# lab_1_zhernakov_usb_rs232.net
KiCad netlist of a schematic drawn in Altium Designer
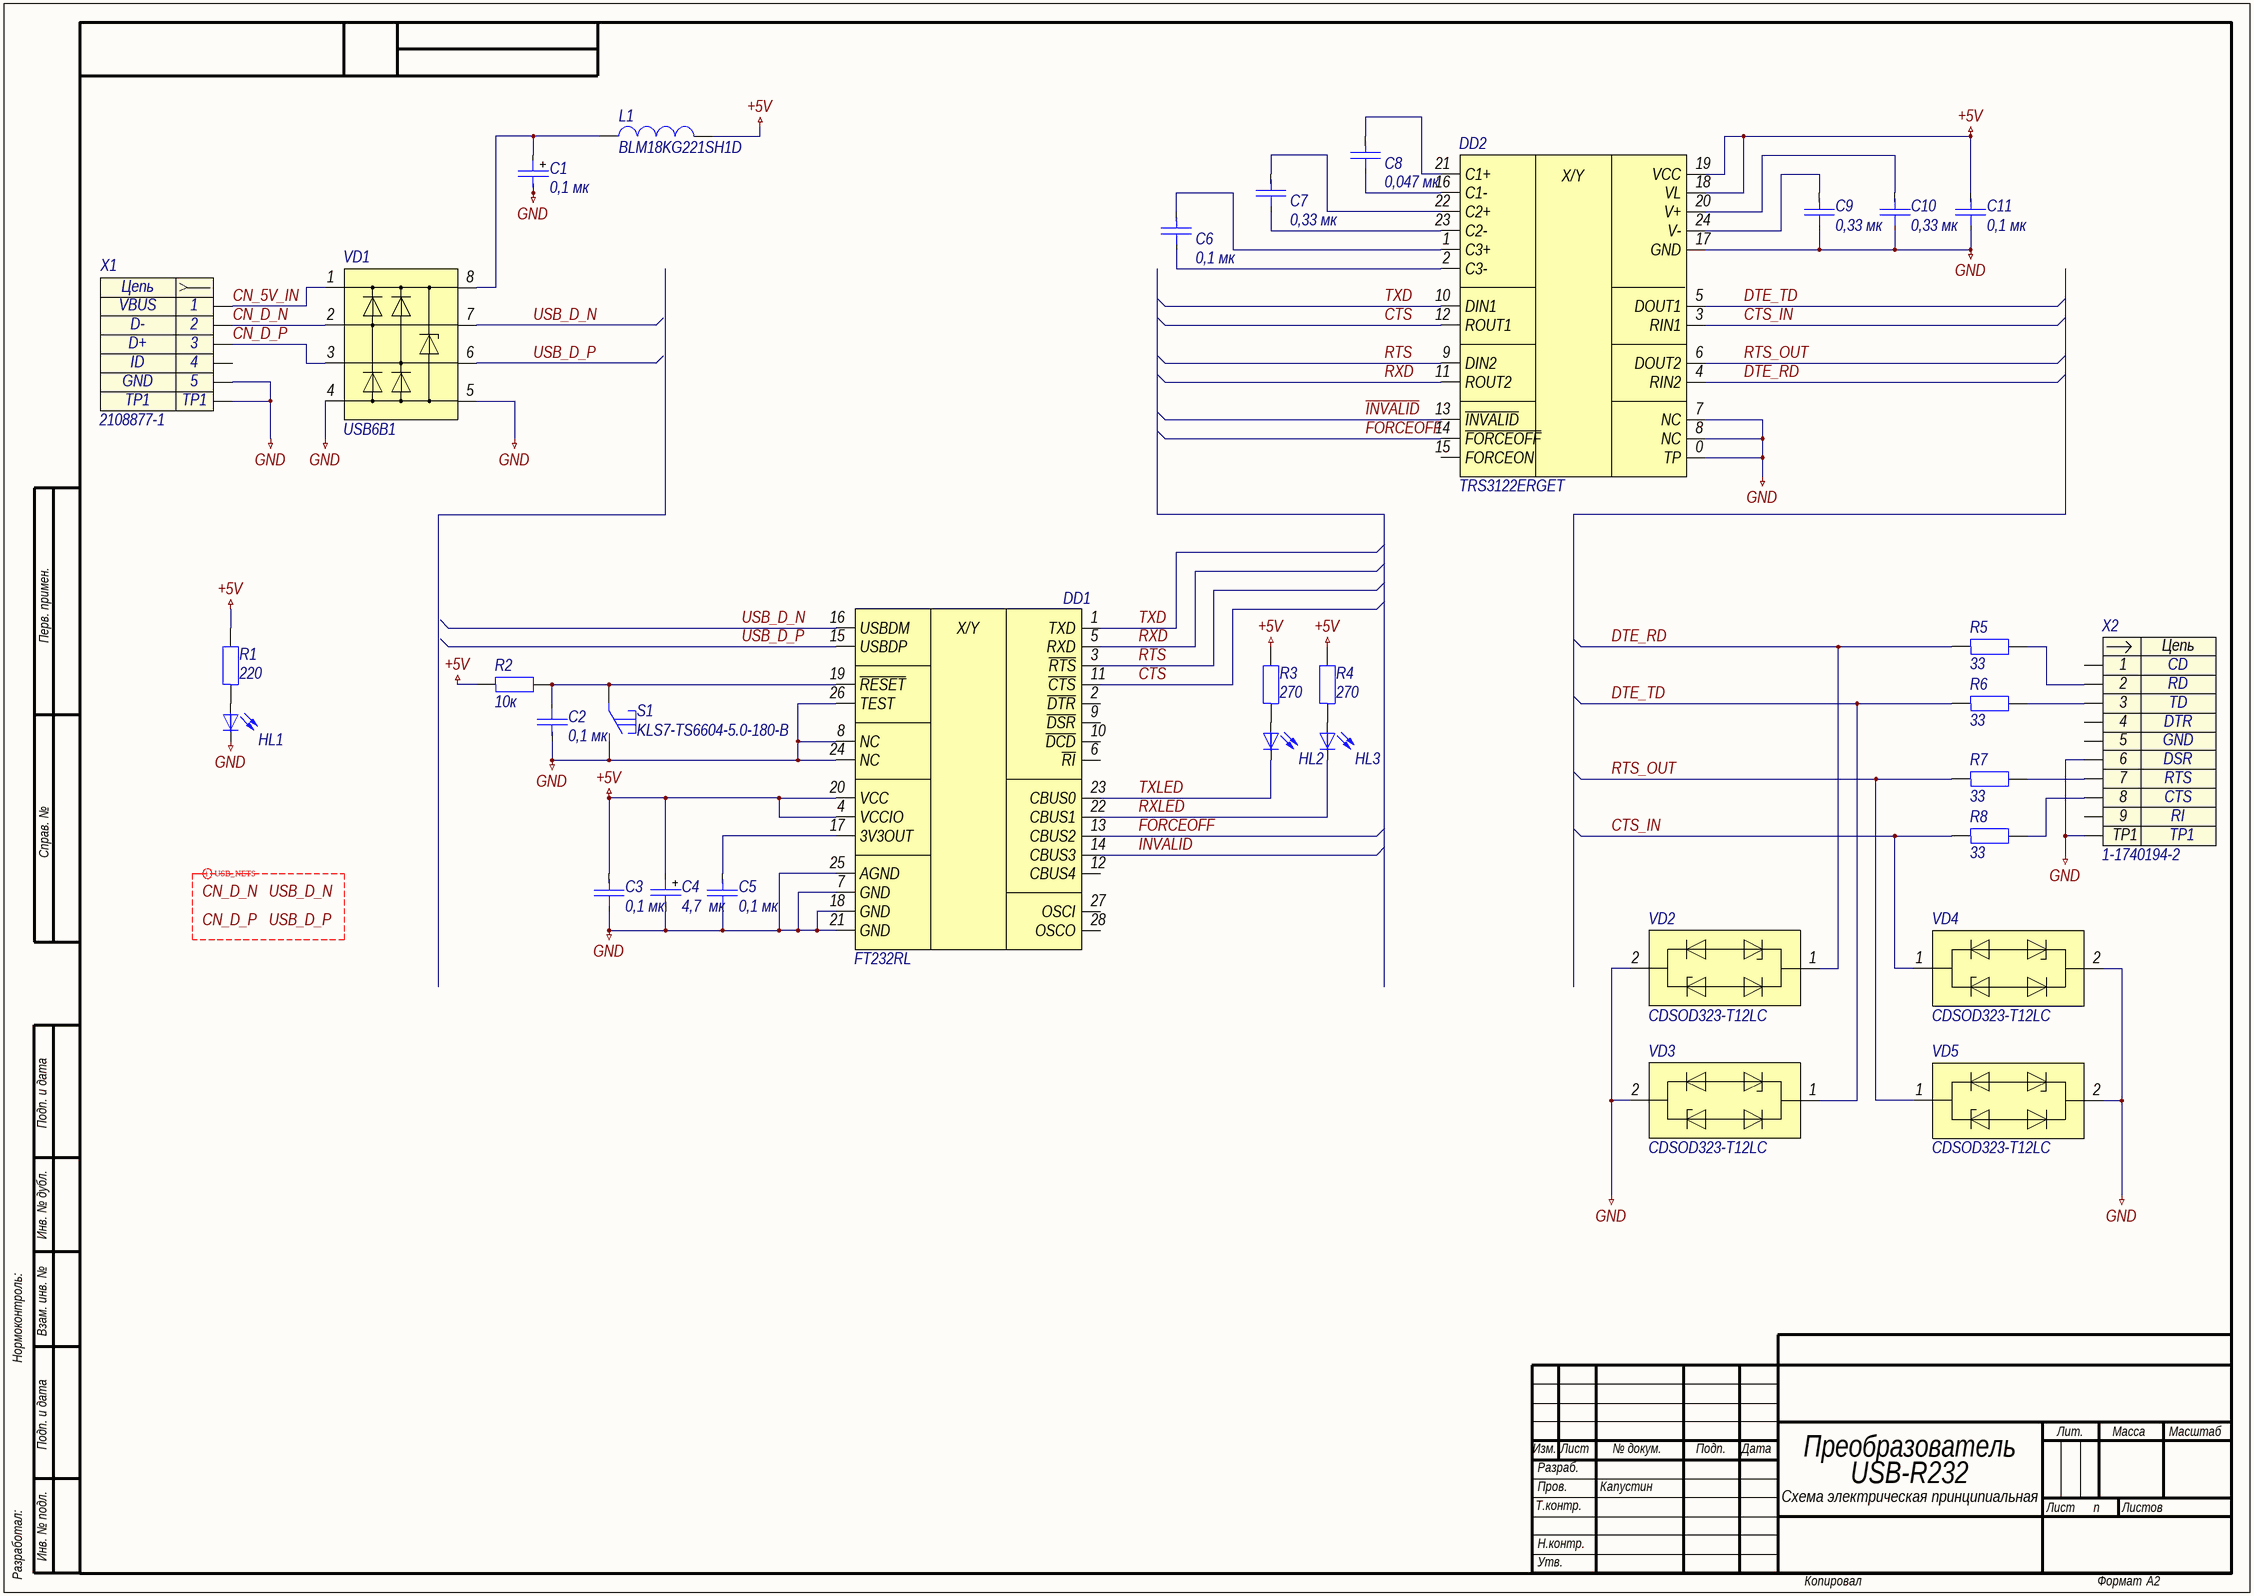
[diagram p0: lab_1_zhernakov_usb_rs232.SchDoc]

(export (version "E")
  (design (tool "Eeschema 10.0.6"))
  (components
    (comp (ref "C1")
      (value "0,1 мк")
      (footprint "C3216-18")
      (description "=Описание")
      (libsource (lib "Database_Students") (part "C-25.0V"))
    )
    (comp (ref "C2")
      (value "0,1 мк")
      (footprint "C0603")
      (description "=Описание")
      (libsource (lib "Database_Students") (part "C-50.0V"))
    )
    (comp (ref "C3")
      (value "0,1 мк")
      (footprint "C0603")
      (description "=Описание")
      (libsource (lib "Database_Students") (part "C-50.0V"))
    )
    (comp (ref "C4")
      (value "4,7  мк")
      (footprint "C3216-18")
      (description "=Описание")
      (libsource (lib "Database_Students") (part "C-25.0V"))
    )
    (comp (ref "C5")
      (value "0,1 мк")
      (footprint "c0805:C0805")
      (description "=Описание")
      (libsource (lib "Database_Students") (part "C-50.0V"))
    )
    (comp (ref "C6")
      (value "0,1 мк")
      (footprint "C0603")
      (description "=Описание")
      (libsource (lib "Database_Students") (part "C-50.0V"))
    )
    (comp (ref "C7")
      (value "0,33 мк")
      (footprint "C0805")
      (description "=Описание")
      (libsource (lib "Database_Students") (part "C-50.0V"))
    )
    (comp (ref "C8")
      (value "0,047 мк")
      (footprint "C0603")
      (description "=Описание")
      (libsource (lib "Database_Students") (part "C-50.0V"))
    )
    (comp (ref "C9")
      (value "0,33 мк")
      (footprint "C0805")
      (description "=Описание")
      (libsource (lib "Database_Students") (part "C-50.0V"))
    )
    (comp (ref "C10")
      (value "0,33 мк")
      (footprint "C0805")
      (description "=Описание")
      (libsource (lib "Database_Students") (part "C-50.0V"))
    )
    (comp (ref "C11")
      (value "0,1 мк")
      (footprint "C0603")
      (description "=Описание")
      (libsource (lib "Database_Students") (part "C-50.0V"))
    )
    (comp (ref "DD1")
      (value "FT232RL")
      (footprint "SSOP-28")
      (description "=Описание")
      (libsource (lib "Database_Students") (part "FT232RL"))
    )
    (comp (ref "DD2")
      (value "TRS3122ERGET")
      (footprint "QFN-24-400x400x100")
      (description "=Описание")
      (libsource (lib "Database_Students") (part "TRS3122ERGET"))
    )
    (comp (ref "HL1")
      (value "~")
      (footprint "D0603")
      (description "=Описание")
      (libsource (lib "Database_Students") (part "L0001"))
    )
    (comp (ref "HL2")
      (value "~")
      (footprint "D0603")
      (description "=Описание")
      (libsource (lib "Database_Students") (part "L0001"))
    )
    (comp (ref "HL3")
      (value "~")
      (footprint "D0603")
      (description "=Описание")
      (libsource (lib "Database_Students") (part "L0001"))
    )
    (comp (ref "L1")
      (value "BLM18KG221SH1D")
      (footprint "FERRITE-BEAD")
      (description "=Описание")
      (libsource (lib "Database_Students") (part "FERRITE-BEAD"))
    )
    (comp (ref "R1")
      (value "220")
      (footprint "R0603")
      (description "=Описание")
      (libsource (lib "Database_Students") (part "R-0.05W"))
    )
    (comp (ref "R2")
      (value "10к")
      (footprint "R0603")
      (description "=Описание")
      (libsource (lib "Database_Students") (part "R-0.05W"))
    )
    (comp (ref "R3")
      (value "270")
      (footprint "R0603")
      (description "=Описание")
      (libsource (lib "Database_Students") (part "R-0.05W"))
    )
    (comp (ref "R4")
      (value "270")
      (footprint "R0603")
      (description "=Описание")
      (libsource (lib "Database_Students") (part "R-0.05W"))
    )
    (comp (ref "R5")
      (value "33")
      (footprint "R0603")
      (description "=Описание")
      (libsource (lib "Database_Students") (part "R-0.05W"))
    )
    (comp (ref "R6")
      (value "33")
      (footprint "R0603")
      (description "=Описание")
      (libsource (lib "Database_Students") (part "R-0.05W"))
    )
    (comp (ref "R7")
      (value "33")
      (footprint "R0603")
      (description "=Описание")
      (libsource (lib "Database_Students") (part "R-0.05W"))
    )
    (comp (ref "R8")
      (value "33")
      (footprint "R0603")
      (description "=Описание")
      (libsource (lib "Database_Students") (part "R-0.05W"))
    )
    (comp (ref "S1")
      (value "KLS7-TS6604-5.0-180-B")
      (footprint "KLS7-TS6604-5.0-180-B")
      (description "=Описание")
      (libsource (lib "Database_Students") (part "BUTTON"))
    )
    (comp (ref "VD1")
      (value "USB6B1")
      (footprint "SO-8")
      (libsource (lib "Database_Students") (part "asmvd0007"))
    )
    (comp (ref "VD2")
      (value "CDSOD323-T12LC")
      (footprint "SOD-323")
      (description "=Описание")
      (libsource (lib "") (part "CDSOD323-T12LC_1"))
    )
    (comp (ref "VD3")
      (value "CDSOD323-T12LC")
      (footprint "SOD-323")
      (description "=Описание")
      (libsource (lib "") (part "CDSOD323-T12LC_1"))
    )
    (comp (ref "VD4")
      (value "CDSOD323-T12LC")
      (footprint "SOD-323")
      (description "=Описание")
      (libsource (lib "Database_Students") (part "CDSOD323-T12LC"))
    )
    (comp (ref "VD5")
      (value "CDSOD323-T12LC")
      (footprint "SOD-323")
      (description "=Описание")
      (libsource (lib "Database_Students") (part "CDSOD323-T12LC"))
    )
    (comp (ref "X1")
      (value "2108877-1")
      (footprint "2108877-1")
      (libsource (lib "2108877-1_micro_usb-b") (part "2108877-1_micro_usb-b"))
    )
    (comp (ref "X2")
      (value "1-1740194-2")
      (footprint "1-1740194-2")
      (libsource (lib "Database_Students") (part "HEADER-9-TP1-SCT"))
    )
  )
  (nets
    (net (code "1") (name "+5V") (class "Default")
      (node (ref "C11") (pin "2") (pinfunction "2_2") (pintype "passive"))
      (node (ref "C3") (pin "2") (pinfunction "2_2") (pintype "passive"))
      (node (ref "C4") (pin "1") (pinfunction "1_1") (pintype "passive"))
      (node (ref "DD1") (pin "20") (pinfunction "VCC_20") (pintype "passive"))
      (node (ref "DD1") (pin "4") (pinfunction "VCCIO_4") (pintype "passive"))
      (node (ref "DD2") (pin "18") (pinfunction "VL_18") (pintype "passive"))
      (node (ref "DD2") (pin "19") (pinfunction "VCC_19") (pintype "passive"))
      (node (ref "L1") (pin "2") (pinfunction "2_2") (pintype "passive"))
      (node (ref "R1") (pin "2") (pinfunction "2_2") (pintype "passive"))
      (node (ref "R2") (pin "1") (pinfunction "1_1") (pintype "passive"))
      (node (ref "R3") (pin "2") (pinfunction "2_2") (pintype "passive"))
      (node (ref "R4") (pin "2") (pinfunction "2_2") (pintype "passive"))
    )
    (net (code "2") (name "/CN_5V_IN") (class "Default")
      (node (ref "VD1") (pin "1") (pintype "passive"))
      (node (ref "X1") (pin "1") (pinfunction "1_1") (pintype "passive"))
    )
    (net (code "3") (name "/CN_D_N") (class "Default")
      (node (ref "VD1") (pin "2") (pintype "passive"))
      (node (ref "X1") (pin "2") (pinfunction "2_2") (pintype "passive"))
    )
    (net (code "4") (name "/CN_D_P") (class "Default")
      (node (ref "VD1") (pin "3") (pintype "passive"))
      (node (ref "X1") (pin "3") (pinfunction "3_3") (pintype "passive"))
    )
    (net (code "5") (name "/CTS") (class "Default")
      (node (ref "DD1") (pin "11") (pinfunction "~{CTS}_11") (pintype "passive"))
      (node (ref "DD2") (pin "12") (pinfunction "ROUT1_12") (pintype "passive"))
    )
    (net (code "6") (name "/CTS_IN") (class "Default")
      (node (ref "DD2") (pin "3") (pinfunction "RIN1_3") (pintype "passive"))
      (node (ref "R8") (pin "1") (pinfunction "1_1") (pintype "passive"))
      (node (ref "VD4") (pin "1") (pintype "passive"))
    )
    (net (code "7") (name "/DTE_RD") (class "Default")
      (node (ref "DD2") (pin "4") (pinfunction "RIN2_4") (pintype "passive"))
      (node (ref "R5") (pin "1") (pinfunction "1_1") (pintype "passive"))
      (node (ref "VD2") (pin "1") (pintype "passive"))
    )
    (net (code "8") (name "/DTE_TD") (class "Default")
      (node (ref "DD2") (pin "5") (pinfunction "DOUT1_5") (pintype "passive"))
      (node (ref "R6") (pin "1") (pinfunction "1_1") (pintype "passive"))
      (node (ref "VD3") (pin "1") (pintype "passive"))
    )
    (net (code "9") (name "/RTS") (class "Default")
      (node (ref "DD1") (pin "3") (pinfunction "~{RTS}_3") (pintype "passive"))
      (node (ref "DD2") (pin "9") (pinfunction "DIN2_9") (pintype "passive"))
    )
    (net (code "10") (name "/RTS_OUT") (class "Default")
      (node (ref "DD2") (pin "6") (pinfunction "DOUT2_6") (pintype "passive"))
      (node (ref "R7") (pin "1") (pinfunction "1_1") (pintype "passive"))
      (node (ref "VD5") (pin "1") (pintype "passive"))
    )
    (net (code "11") (name "/RXD") (class "Default")
      (node (ref "DD1") (pin "5") (pinfunction "RXD_5") (pintype "passive"))
      (node (ref "DD2") (pin "11") (pinfunction "ROUT2_11") (pintype "passive"))
    )
    (net (code "12") (name "/RXLED") (class "Default")
      (node (ref "DD1") (pin "22") (pinfunction "CBUS1_22") (pintype "passive"))
      (node (ref "HL3") (pin "2") (pinfunction "K_2") (pintype "passive"))
    )
    (net (code "13") (name "/TXD") (class "Default")
      (node (ref "DD1") (pin "1") (pinfunction "TXD_1") (pintype "passive"))
      (node (ref "DD2") (pin "10") (pinfunction "DIN1_10") (pintype "passive"))
    )
    (net (code "14") (name "/TXLED") (class "Default")
      (node (ref "DD1") (pin "23") (pinfunction "CBUS0_23") (pintype "passive"))
      (node (ref "HL2") (pin "2") (pinfunction "K_2") (pintype "passive"))
    )
    (net (code "15") (name "/USB_D_N") (class "Default")
      (node (ref "DD1") (pin "16") (pinfunction "USBDM_16") (pintype "passive"))
      (node (ref "VD1") (pin "7") (pintype "passive"))
    )
    (net (code "16") (name "/USB_D_P") (class "Default")
      (node (ref "DD1") (pin "15") (pinfunction "USBDP_15") (pintype "passive"))
      (node (ref "VD1") (pin "6") (pintype "passive"))
    )
    (net (code "17") (name "/~{FORCEOFF}") (class "Default")
      (node (ref "DD1") (pin "13") (pinfunction "CBUS2_13") (pintype "passive"))
      (node (ref "DD2") (pin "14") (pinfunction "~{FORCEOFF}_14") (pintype "passive"))
    )
    (net (code "18") (name "/~{INVALID}") (class "Default")
      (node (ref "DD1") (pin "14") (pinfunction "CBUS3_14") (pintype "passive"))
      (node (ref "DD2") (pin "13") (pinfunction "~{INVALID}_13") (pintype "passive"))
    )
    (net (code "19") (name "GND") (class "Default")
      (node (ref "C1") (pin "2") (pinfunction "2_2") (pintype "passive"))
      (node (ref "C10") (pin "1") (pinfunction "1_1") (pintype "passive"))
      (node (ref "C11") (pin "1") (pinfunction "1_1") (pintype "passive"))
      (node (ref "C2") (pin "2") (pinfunction "2_2") (pintype "passive"))
      (node (ref "C3") (pin "1") (pinfunction "1_1") (pintype "passive"))
      (node (ref "C4") (pin "2") (pinfunction "2_2") (pintype "passive"))
      (node (ref "C5") (pin "1") (pinfunction "1_1") (pintype "passive"))
      (node (ref "C9") (pin "1") (pinfunction "1_1") (pintype "passive"))
      (node (ref "DD1") (pin "18") (pinfunction "GND_18") (pintype "passive"))
      (node (ref "DD1") (pin "21") (pinfunction "GND_21") (pintype "passive"))
      (node (ref "DD1") (pin "24") (pinfunction "NC_24") (pintype "passive"))
      (node (ref "DD1") (pin "25") (pinfunction "AGND_25") (pintype "passive"))
      (node (ref "DD1") (pin "26") (pinfunction "TEST_26") (pintype "passive"))
      (node (ref "DD1") (pin "7") (pinfunction "GND_7") (pintype "passive"))
      (node (ref "DD1") (pin "8") (pinfunction "NC_8") (pintype "passive"))
      (node (ref "DD2") (pin "0") (pinfunction "TP_0") (pintype "passive"))
      (node (ref "DD2") (pin "17") (pinfunction "GND_17") (pintype "passive"))
      (node (ref "DD2") (pin "7") (pinfunction "NC_7") (pintype "passive"))
      (node (ref "DD2") (pin "8") (pinfunction "NC_8") (pintype "passive"))
      (node (ref "HL1") (pin "2") (pinfunction "K_2") (pintype "passive"))
      (node (ref "S1") (pin "2") (pinfunction "2_2") (pintype "passive"))
      (node (ref "VD1") (pin "4") (pintype "passive"))
      (node (ref "VD1") (pin "5") (pintype "passive"))
      (node (ref "VD2") (pin "2") (pintype "passive"))
      (node (ref "VD3") (pin "2") (pintype "passive"))
      (node (ref "VD4") (pin "2") (pintype "passive"))
      (node (ref "VD5") (pin "2") (pintype "passive"))
      (node (ref "X1") (pin "5") (pinfunction "5_5") (pintype "passive"))
      (node (ref "X1") (pin "TP1") (pinfunction "TP1_TP1") (pintype "passive"))
      (node (ref "X2") (pin "6") (pinfunction "6_6") (pintype "passive"))
      (node (ref "X2") (pin "TP1") (pinfunction "TP1_TP1") (pintype "passive"))
    )
    (net (code "20") (name "Net-(C1-Pad1)") (class "Default")
      (node (ref "C1") (pin "1") (pinfunction "1_1") (pintype "passive"))
      (node (ref "L1") (pin "1") (pinfunction "1_1") (pintype "passive"))
      (node (ref "VD1") (pin "8") (pintype "passive"))
    )
    (net (code "21") (name "Net-(DD1-3V3OUT)") (class "Default")
      (node (ref "C5") (pin "2") (pinfunction "2_2") (pintype "passive"))
      (node (ref "DD1") (pin "17") (pinfunction "3V3OUT_17") (pintype "passive"))
    )
    (net (code "22") (name "Net-(DD1-~{RESET})") (class "Default")
      (node (ref "C2") (pin "1") (pinfunction "1_1") (pintype "passive"))
      (node (ref "DD1") (pin "19") (pinfunction "~{RESET}_19") (pintype "passive"))
      (node (ref "R2") (pin "2") (pinfunction "2_2") (pintype "passive"))
      (node (ref "S1") (pin "1") (pinfunction "1_1") (pintype "passive"))
    )
    (net (code "23") (name "Net-(DD2-C1+)") (class "Default")
      (node (ref "C8") (pin "2") (pinfunction "2_2") (pintype "passive"))
      (node (ref "DD2") (pin "21") (pinfunction "C1+_21") (pintype "passive"))
    )
    (net (code "24") (name "Net-(DD2-C1-)") (class "Default")
      (node (ref "C8") (pin "1") (pinfunction "1_1") (pintype "passive"))
      (node (ref "DD2") (pin "16") (pinfunction "C1-_16") (pintype "passive"))
    )
    (net (code "25") (name "Net-(DD2-C2+)") (class "Default")
      (node (ref "C7") (pin "2") (pinfunction "2_2") (pintype "passive"))
      (node (ref "DD2") (pin "22") (pinfunction "C2+_22") (pintype "passive"))
    )
    (net (code "26") (name "Net-(DD2-C2-)") (class "Default")
      (node (ref "C7") (pin "1") (pinfunction "1_1") (pintype "passive"))
      (node (ref "DD2") (pin "23") (pinfunction "C2-_23") (pintype "passive"))
    )
    (net (code "27") (name "Net-(DD2-C3+)") (class "Default")
      (node (ref "C6") (pin "2") (pinfunction "2_2") (pintype "passive"))
      (node (ref "DD2") (pin "1") (pinfunction "C3+_1") (pintype "passive"))
    )
    (net (code "28") (name "Net-(DD2-C3-)") (class "Default")
      (node (ref "C6") (pin "1") (pinfunction "1_1") (pintype "passive"))
      (node (ref "DD2") (pin "2") (pinfunction "C3-_2") (pintype "passive"))
    )
    (net (code "29") (name "Net-(DD2-V+)") (class "Default")
      (node (ref "C10") (pin "2") (pinfunction "2_2") (pintype "passive"))
      (node (ref "DD2") (pin "20") (pinfunction "V+_20") (pintype "passive"))
    )
    (net (code "30") (name "Net-(DD2-V-)") (class "Default")
      (node (ref "C9") (pin "2") (pinfunction "2_2") (pintype "passive"))
      (node (ref "DD2") (pin "24") (pinfunction "V-_24") (pintype "passive"))
    )
    (net (code "31") (name "Net-(HL1-A)") (class "Default")
      (node (ref "HL1") (pin "1") (pinfunction "A_1") (pintype "passive"))
      (node (ref "R1") (pin "1") (pinfunction "1_1") (pintype "passive"))
    )
    (net (code "32") (name "Net-(HL2-A)") (class "Default")
      (node (ref "HL2") (pin "1") (pinfunction "A_1") (pintype "passive"))
      (node (ref "R3") (pin "1") (pinfunction "1_1") (pintype "passive"))
    )
    (net (code "33") (name "Net-(HL3-A)") (class "Default")
      (node (ref "HL3") (pin "1") (pinfunction "A_1") (pintype "passive"))
      (node (ref "R4") (pin "1") (pinfunction "1_1") (pintype "passive"))
    )
    (net (code "34") (name "Net-(R5-Pad2)") (class "Default")
      (node (ref "R5") (pin "2") (pinfunction "2_2") (pintype "passive"))
      (node (ref "X2") (pin "2") (pinfunction "2_2") (pintype "passive"))
    )
    (net (code "35") (name "Net-(R6-Pad2)") (class "Default")
      (node (ref "R6") (pin "2") (pinfunction "2_2") (pintype "passive"))
      (node (ref "X2") (pin "3") (pinfunction "3_3") (pintype "passive"))
    )
    (net (code "36") (name "Net-(R7-Pad2)") (class "Default")
      (node (ref "R7") (pin "2") (pinfunction "2_2") (pintype "passive"))
      (node (ref "X2") (pin "7") (pinfunction "7_7") (pintype "passive"))
    )
    (net (code "37") (name "Net-(R8-Pad2)") (class "Default")
      (node (ref "R8") (pin "2") (pinfunction "2_2") (pintype "passive"))
      (node (ref "X2") (pin "8") (pinfunction "8_8") (pintype "passive"))
    )
    (net (code "38") (name "unconnected-(DD1-CBUS4-Pad12)") (class "Default")
      (node (ref "DD1") (pin "12") (pinfunction "CBUS4_12") (pintype "passive"))
    )
    (net (code "39") (name "unconnected-(DD1-OSCI-Pad27)") (class "Default")
      (node (ref "DD1") (pin "27") (pinfunction "OSCI_27") (pintype "passive"))
    )
    (net (code "40") (name "unconnected-(DD1-OSCO-Pad28)") (class "Default")
      (node (ref "DD1") (pin "28") (pinfunction "OSCO_28") (pintype "passive"))
    )
    (net (code "41") (name "unconnected-(DD1-~{DCD}-Pad10)") (class "Default")
      (node (ref "DD1") (pin "10") (pinfunction "~{DCD}_10") (pintype "passive"))
    )
    (net (code "42") (name "unconnected-(DD1-~{DSR}-Pad9)") (class "Default")
      (node (ref "DD1") (pin "9") (pinfunction "~{DSR}_9") (pintype "passive"))
    )
    (net (code "43") (name "unconnected-(DD1-~{DTR}-Pad2)") (class "Default")
      (node (ref "DD1") (pin "2") (pinfunction "~{DTR}_2") (pintype "passive"))
    )
    (net (code "44") (name "unconnected-(DD1-~{RI}-Pad6)") (class "Default")
      (node (ref "DD1") (pin "6") (pinfunction "~{RI}_6") (pintype "passive"))
    )
    (net (code "45") (name "unconnected-(DD2-FORCEON-Pad15)") (class "Default")
      (node (ref "DD2") (pin "15") (pinfunction "FORCEON_15") (pintype "passive"))
    )
    (net (code "46") (name "unconnected-(X1-Pad4)") (class "Default")
      (node (ref "X1") (pin "4") (pinfunction "4_4") (pintype "passive"))
    )
    (net (code "47") (name "unconnected-(X2-Pad1)") (class "Default")
      (node (ref "X2") (pin "1") (pinfunction "1_1") (pintype "passive"))
    )
    (net (code "48") (name "unconnected-(X2-Pad4)") (class "Default")
      (node (ref "X2") (pin "4") (pinfunction "4_4") (pintype "passive"))
    )
    (net (code "49") (name "unconnected-(X2-Pad5)") (class "Default")
      (node (ref "X2") (pin "5") (pinfunction "5_5") (pintype "passive"))
    )
    (net (code "50") (name "unconnected-(X2-Pad9)") (class "Default")
      (node (ref "X2") (pin "9") (pinfunction "9_9") (pintype "passive"))
    )
  )
)
